# Supplies.net
KiCad netlist of a schematic drawn in Altium Designer
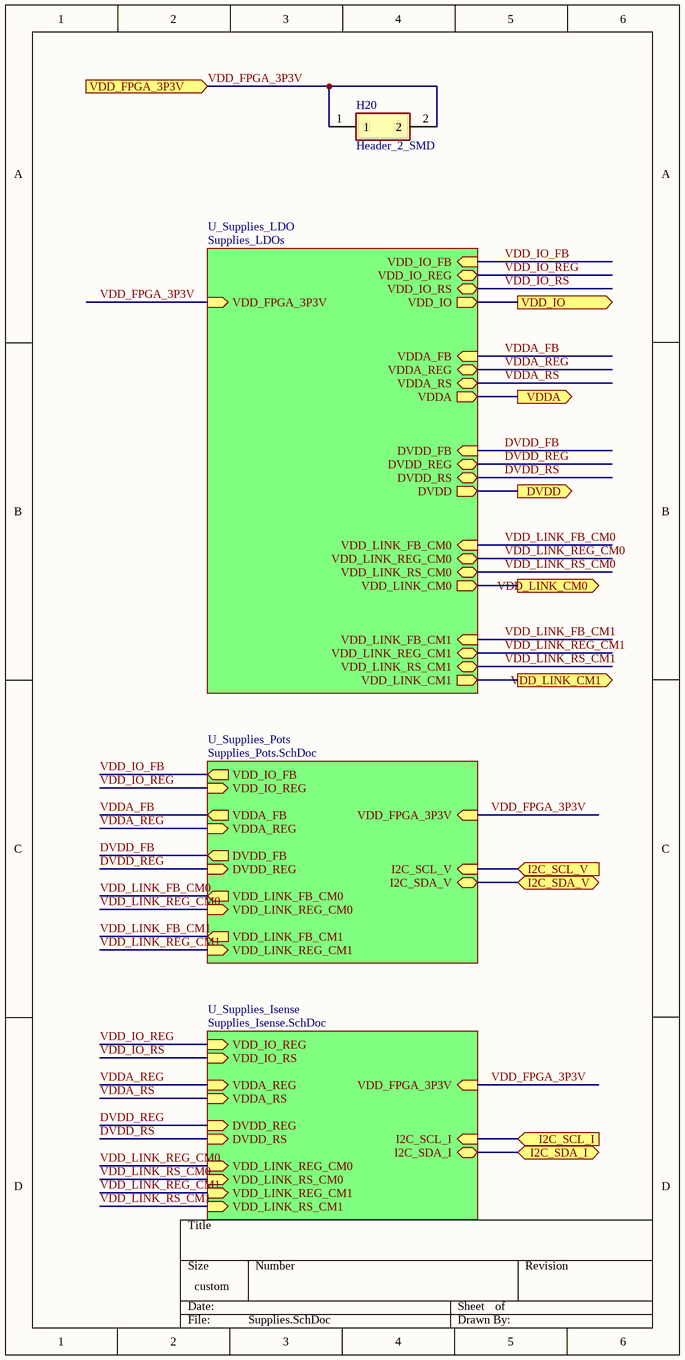
[diagram p0: Supplies.SchDoc]

(export (version "E")
  (design (tool "Eeschema 10.0.6"))
  (components
    (comp (ref "H20")
      (value "Header_2_SMD")
      (footprint "HDR1X2_SMD_S")
      (description "Connector Header Vertical, SMD, 2 position 0.100\" (2.54mm)")
      (fields
        (field (name "MANUFACTURER_PART_NUMBER") "TSM-102-01-S-SV")
        (field (name "MOUSER PART NUMBER") "200-TSM10201SSV")
      )
      (libsource (lib "fader2_parts") (part "Header_2_SMD"))
    )
  )
  (nets
    (net (code "13") (name "/VDD_FPGA_3P3V") (class "Default")
      (node (ref "H20") (pin "1") (pinfunction "1_1") (pintype "passive"))
      (node (ref "H20") (pin "2") (pinfunction "2_2") (pintype "passive"))
    )
  )
)
